# AWR2243_PMIC.net
KiCad netlist of a schematic drawn in Altium Designer
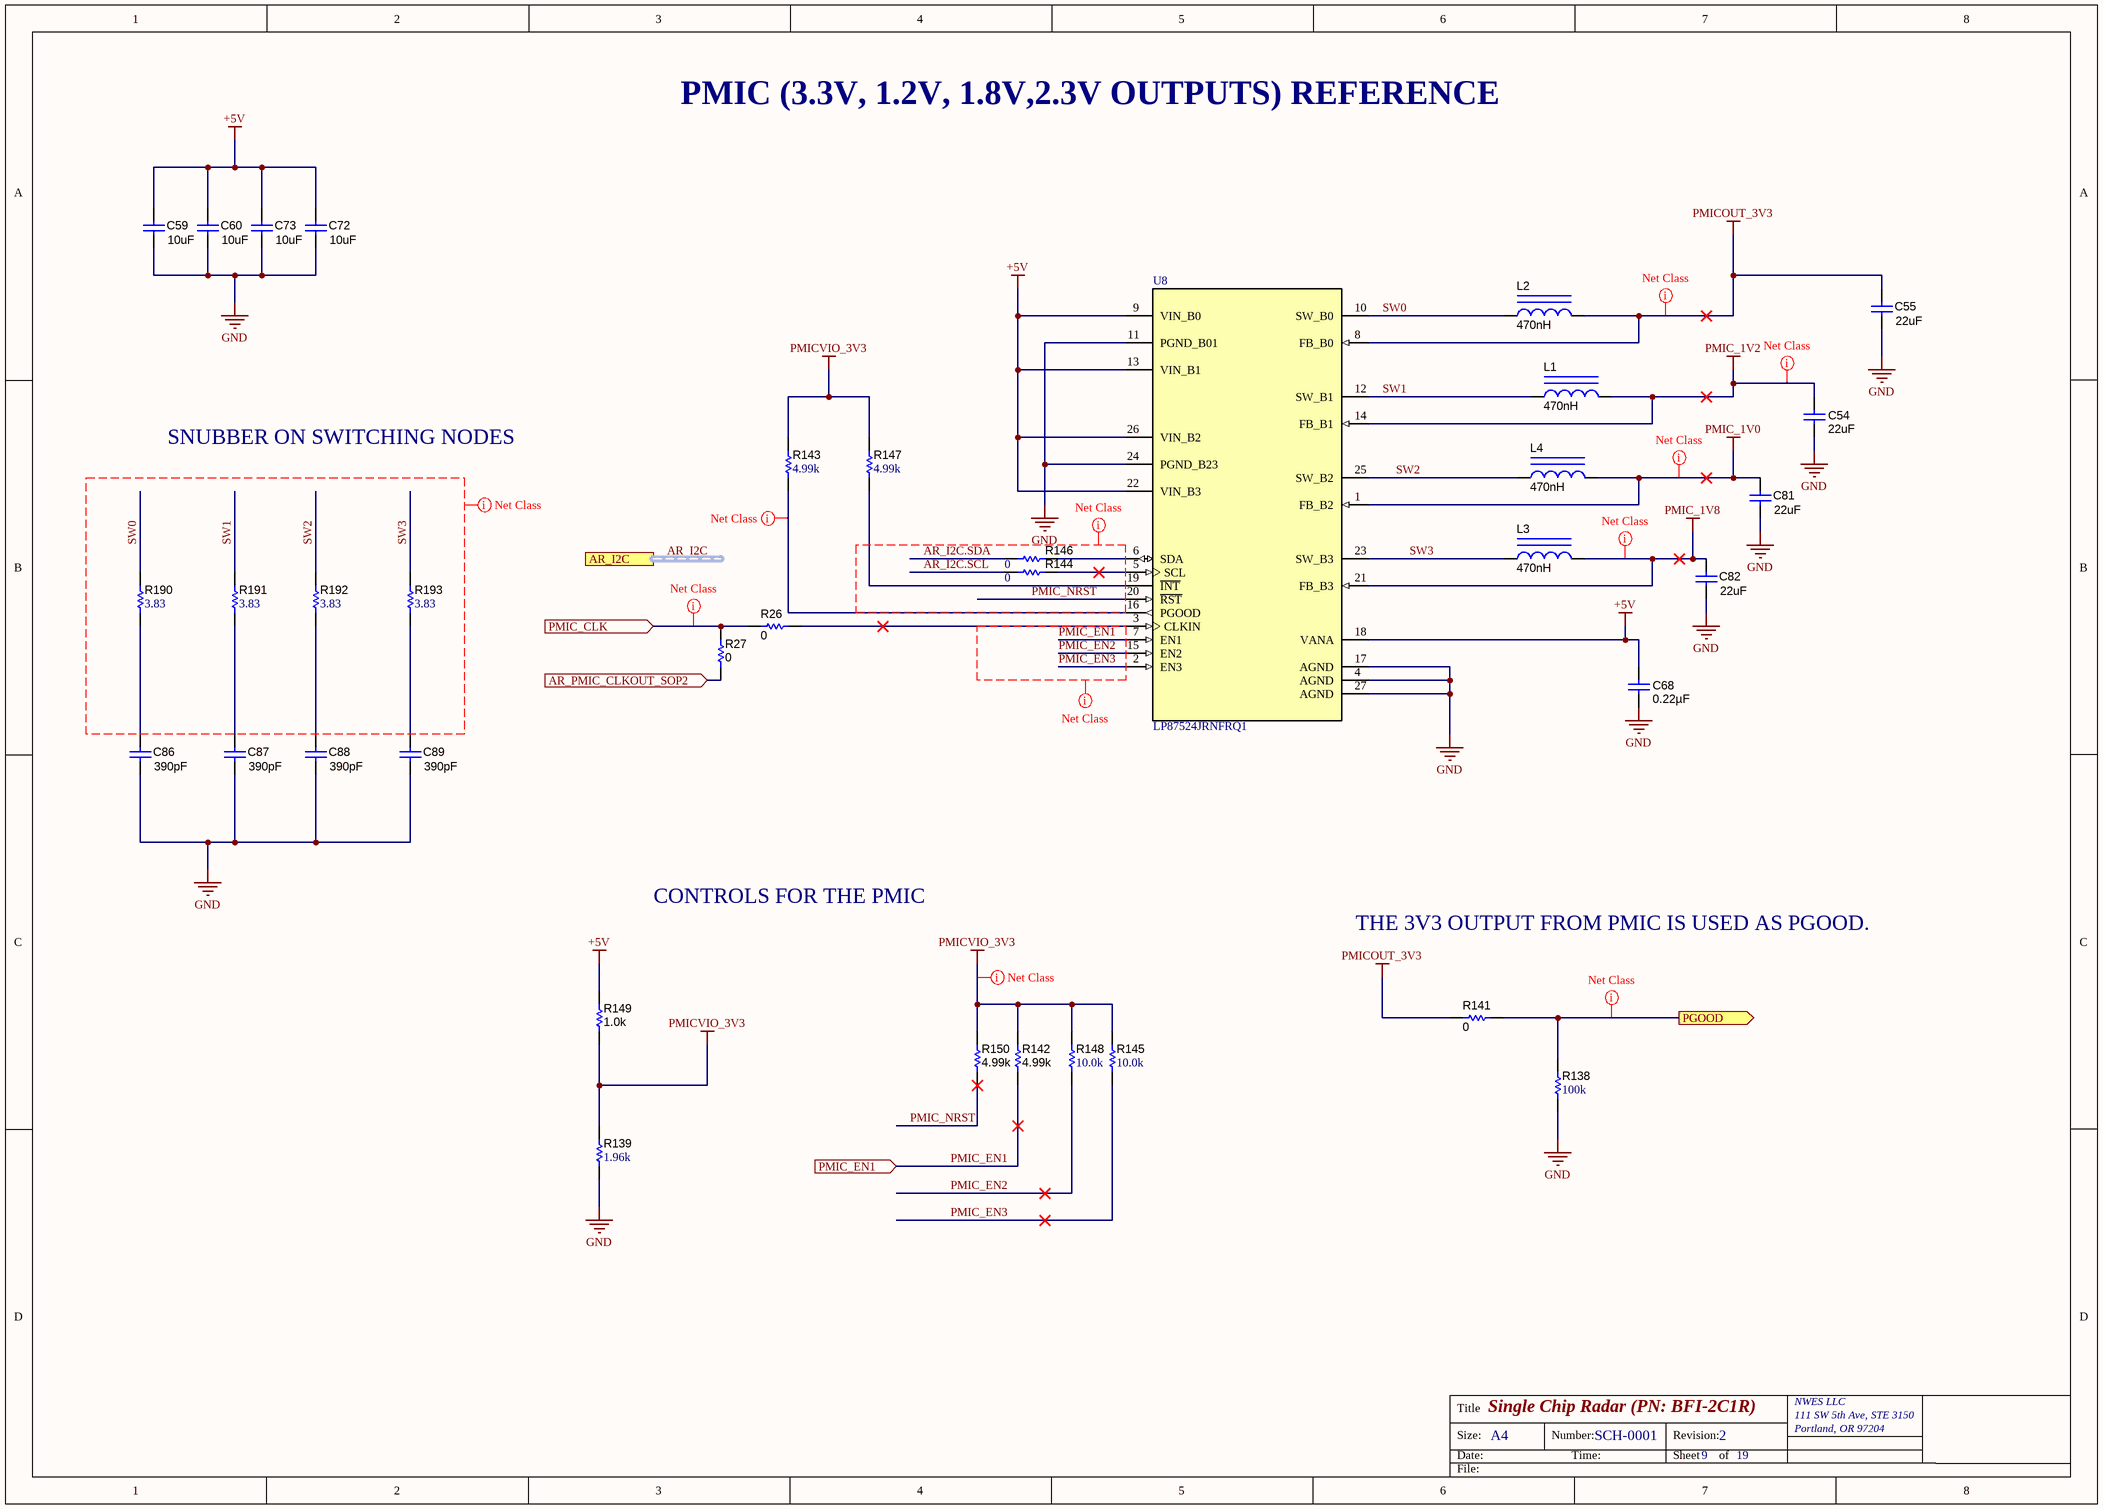
[diagram p0: AWR2243_PMIC.SchDoc]

(export (version "E")
  (design (tool "Eeschema 10.0.6"))
  (components
    (comp (ref "C54")
      (value "GCM31CR71A226KE02")
      (footprint "1206_180")
      (description "CAP, CERM, 22 uF, 10 V, +/- 10%, X7R, AEC-Q200 Grade 1, 1206")
      (fields
        (field (name "MANUFACTURER") "MuRata")
        (field (name "VALUEDISPLAYED") "22uF")
        (field (name "PUBLISHER") "Texas Instruments")
      )
      (libsource (lib "Altium Vault - TI") (part "CMP-0008811-2"))
    )
    (comp (ref "C55")
      (value "GCM31CR71A226KE02")
      (footprint "1206_180")
      (description "CAP, CERM, 22 uF, 10 V, +/- 10%, X7R, AEC-Q200 Grade 1, 1206")
      (fields
        (field (name "MANUFACTURER") "MuRata")
        (field (name "VALUEDISPLAYED") "22uF")
        (field (name "PUBLISHER") "Texas Instruments")
      )
      (libsource (lib "Altium Vault - TI") (part "Capacitor"))
    )
    (comp (ref "C59")
      (value "GCM21BR71A106KE22L")
      (footprint "0805_HV1")
      (description "CAP, CERM, 10 uF, 10 V, +/- 10%, X7R, 0805")
      (fields
        (field (name "MANUFACTURER") "MuRata")
        (field (name "VALUEDISPLAYED") "10uF")
        (field (name "PUBLISHER") "Texas Instruments")
      )
      (libsource (lib "Altium Vault - TI") (part "CMP-0008017-2"))
    )
    (comp (ref "C60")
      (value "GCM21BR71A106KE22L")
      (footprint "0805_HV1")
      (description "CAP, CERM, 10 uF, 10 V, +/- 10%, X7R, 0805")
      (fields
        (field (name "MANUFACTURER") "MuRata")
        (field (name "VALUEDISPLAYED") "10uF")
        (field (name "PUBLISHER") "Texas Instruments")
      )
      (libsource (lib "Altium Vault - TI") (part "CMP-0008017-2"))
    )
    (comp (ref "C68")
      (value "GCM155R71C224KE02D")
      (footprint "0402L")
      (description "CAP, CERM, 0.22 µF, 16 V,+/- 10%, X7R, AEC-Q200 Grade 1, 0402")
      (fields (field (name "MANUFACTURER") "MuRata") (field (name "VALUEDISPLAYED") "0.22µF"))
      (libsource (lib "Altium Vault - TI") (part "CMP-0078265-1"))
    )
    (comp (ref "C72")
      (value "GCM21BR71A106KE22L")
      (footprint "0805_HV1")
      (description "CAP, CERM, 10 uF, 10 V, +/- 10%, X7R, 0805")
      (fields
        (field (name "MANUFACTURER") "MuRata")
        (field (name "VALUEDISPLAYED") "10uF")
        (field (name "PUBLISHER") "Texas Instruments")
      )
      (libsource (lib "Altium Vault - TI") (part "CMP-0008017-2"))
    )
    (comp (ref "C73")
      (value "GCM21BR71A106KE22L")
      (footprint "0805_HV1")
      (description "CAP, CERM, 10 uF, 10 V, +/- 10%, X7R, 0805")
      (fields
        (field (name "MANUFACTURER") "MuRata")
        (field (name "VALUEDISPLAYED") "10uF")
        (field (name "PUBLISHER") "Texas Instruments")
      )
      (libsource (lib "Altium Vault - TI") (part "CMP-0008017-2"))
    )
    (comp (ref "C81")
      (value "GCM31CR71A226KE02")
      (footprint "1206_180")
      (description "CAP, CERM, 22 uF, 10 V, +/- 10%, X7R, AEC-Q200 Grade 1, 1206")
      (fields
        (field (name "MANUFACTURER") "MuRata")
        (field (name "VALUEDISPLAYED") "22uF")
        (field (name "PUBLISHER") "Texas Instruments")
      )
      (libsource (lib "Altium Vault - TI") (part "Capacitor"))
    )
    (comp (ref "C82")
      (value "GCM31CR71A226KE02")
      (footprint "1206_180")
      (description "CAP, CERM, 22 uF, 10 V, +/- 10%, X7R, AEC-Q200 Grade 1, 1206")
      (fields
        (field (name "MANUFACTURER") "MuRata")
        (field (name "VALUEDISPLAYED") "22uF")
        (field (name "PUBLISHER") "Texas Instruments")
      )
      (libsource (lib "Altium Vault - TI") (part "Capacitor"))
    )
    (comp (ref "C86")
      (value "GRM1555C1H391JA01D")
      (footprint "0402")
      (description "CAP, CERM, 390 pF, 50 V, +/- 5%, C0G/NP0, 0402")
      (fields
        (field (name "MANUFACTURER") "MuRata")
        (field (name "VALUEDISPLAYED") "390pF")
        (field (name "PUBLISHER") "Texas Instruments")
      )
      (libsource (lib "Altium Vault - TI") (part "Capacitor"))
    )
    (comp (ref "C87")
      (value "GRM1555C1H391JA01D")
      (footprint "0402")
      (description "CAP, CERM, 390 pF, 50 V, +/- 5%, C0G/NP0, 0402")
      (fields
        (field (name "MANUFACTURER") "MuRata")
        (field (name "VALUEDISPLAYED") "390pF")
        (field (name "PUBLISHER") "Texas Instruments")
      )
      (libsource (lib "Altium Vault - TI") (part "Capacitor"))
    )
    (comp (ref "C88")
      (value "GRM1555C1H391JA01D")
      (footprint "0402")
      (description "CAP, CERM, 390 pF, 50 V, +/- 5%, C0G/NP0, 0402")
      (fields
        (field (name "MANUFACTURER") "MuRata")
        (field (name "VALUEDISPLAYED") "390pF")
        (field (name "PUBLISHER") "Texas Instruments")
      )
      (libsource (lib "Altium Vault - TI") (part "Capacitor"))
    )
    (comp (ref "C89")
      (value "GRM1555C1H391JA01D")
      (footprint "0402")
      (description "CAP, CERM, 390 pF, 50 V, +/- 5%, C0G/NP0, 0402")
      (fields
        (field (name "MANUFACTURER") "MuRata")
        (field (name "VALUEDISPLAYED") "390pF")
        (field (name "PUBLISHER") "Texas Instruments")
      )
      (libsource (lib "Altium Vault - TI") (part "Capacitor"))
    )
    (comp (ref "L1")
      (value "DFE252012P-R47M=P2")
      (footprint "DFE252012P")
      (description "Inductor, Shielded, 470 nH, 4.7 A, 0.021 ohm, SMD")
      (fields
        (field (name "MANUFACTURER") "MuRata Toko")
        (field (name "VALUEDISPLAYED") "470nH")
        (field (name "PUBLISHER") "Texas Instruments")
      )
      (libsource (lib "Altium Vault - TI") (part "Inductor_Iron"))
    )
    (comp (ref "L2")
      (value "DFE252012P-R47M=P2")
      (footprint "DFE252012P")
      (description "Inductor, Shielded, 470 nH, 4.7 A, 0.021 ohm, SMD")
      (fields
        (field (name "MANUFACTURER") "MuRata Toko")
        (field (name "VALUEDISPLAYED") "470nH")
        (field (name "PUBLISHER") "Texas Instruments")
      )
      (libsource (lib "Altium Vault - TI") (part "Inductor_Iron"))
    )
    (comp (ref "L3")
      (value "DFE252012P-R47M=P2")
      (footprint "DFE252012P")
      (description "Inductor, Shielded, 470 nH, 4.7 A, 0.021 ohm, SMD")
      (fields
        (field (name "MANUFACTURER") "MuRata Toko")
        (field (name "VALUEDISPLAYED") "470nH")
        (field (name "PUBLISHER") "Texas Instruments")
      )
      (libsource (lib "Altium Vault - TI") (part "Inductor_Iron"))
    )
    (comp (ref "L4")
      (value "DFE252012P-R47M=P2")
      (footprint "DFE252012P")
      (description "Inductor, Shielded, 470 nH, 4.7 A, 0.021 ohm, SMD")
      (fields
        (field (name "MANUFACTURER") "MuRata Toko")
        (field (name "VALUEDISPLAYED") "470nH")
        (field (name "PUBLISHER") "Texas Instruments")
      )
      (libsource (lib "Altium Vault - TI") (part "Inductor_Iron"))
    )
    (comp (ref "R26")
      (value "ERJ-2GE0R00X")
      (footprint "0402")
      (description "RES, 0, 5%, 0.063 W, 0402")
      (fields
        (field (name "MANUFACTURER") "Panasonic")
        (field (name "VALUEDISPLAYED") "0")
        (field (name "PUBLISHER") "Texas Instruments")
      )
      (libsource (lib "Radar FPGA RF") (part "CMP-0026992-2"))
    )
    (comp (ref "R27")
      (value "ERJ-2GE0R00X")
      (footprint "0402")
      (description "RES, 0, 5%, 0.063 W, 0402")
      (fields
        (field (name "MANUFACTURER") "Panasonic")
        (field (name "VALUEDISPLAYED") "0")
        (field (name "PUBLISHER") "Texas Instruments")
      )
      (libsource (lib "Radar FPGA RF") (part "CMP-0026992-2"))
    )
    (comp (ref "R138")
      (value "CRCW0402100KFKED")
      (footprint "0402L")
      (description "RES, 100 k, 1%, 0.063 W, AEC-Q200 Grade 0, 0402")
      (fields (field (name "MANUFACTURER") "Vishay-Dale") (field (name "VALUEDISPLAYED") "100k"))
      (libsource (lib "Altium Vault - TI") (part "Resistor"))
    )
    (comp (ref "R139")
      (value "CRCW04021K96FKED")
      (footprint "0402L")
      (description "RES, 1.96 k, 1%, 0.063 W, AEC-Q200 Grade 0, 0402")
      (fields (field (name "MANUFACTURER") "Vishay-Dale") (field (name "VALUEDISPLAYED") "1.96k"))
      (libsource (lib "Altium Vault - TI") (part "Resistor"))
    )
    (comp (ref "R141")
      (value "ERJ-2GE0R00X")
      (footprint "0402L")
      (description "RES, 0, 5%, 0.063 W, 0402")
      (fields
        (field (name "MANUFACTURER") "Panasonic")
        (field (name "VALUEDISPLAYED") "0")
        (field (name "PUBLISHER") "Texas Instruments")
      )
      (libsource (lib "Altium Vault - TI") (part "Resistor"))
    )
    (comp (ref "R142")
      (value "ERJ-2RKF4991X")
      (footprint "0402L")
      (description "RES, 4.99 k, 1%, 0.1 W, AEC-Q200 Grade 0, 0402")
      (fields
        (field (name "MANUFACTURER") "Panasonic")
        (field (name "VALUEDISPLAYED") "4.99k")
        (field (name "PUBLISHER") "Texas Instruments")
      )
      (libsource (lib "Altium Vault - TI") (part "Resistor"))
    )
    (comp (ref "R143")
      (value "CRCW04024K99FKED")
      (footprint "0402L")
      (description "RES, 4.99 k, 1%, 0.063 W, AEC-Q200 Grade 0, 0402")
      (fields (field (name "MANUFACTURER") "Vishay-Dale") (field (name "VALUEDISPLAYED") "4.99k"))
      (libsource (lib "Altium Vault - TI") (part "Resistor"))
    )
    (comp (ref "R144")
      (value "CRCW02010000Z0ED")
      (footprint "0201_Silk")
      (description "RES, 0, 5%, 0.05 W, 0201")
      (fields (field (name "MANUFACTURER") "Vishay-Dale") (field (name "VALUEDISPLAYED") "0"))
      (libsource (lib "Altium Vault - TI") (part "Resistor"))
    )
    (comp (ref "R145")
      (value "CRCW040210K0FKED")
      (footprint "0402L")
      (description "RES, 10.0 k, 1%, 0.063 W, AEC-Q200 Grade 0, 0402")
      (fields (field (name "MANUFACTURER") "Vishay-Dale") (field (name "VALUEDISPLAYED") "10.0k"))
      (libsource (lib "Altium Vault - TI") (part "CMP-0025958-3"))
    )
    (comp (ref "R146")
      (value "CRCW02010000Z0ED")
      (footprint "0201_Silk")
      (description "RES, 0, 5%, 0.05 W, 0201")
      (fields (field (name "MANUFACTURER") "Vishay-Dale") (field (name "VALUEDISPLAYED") "0"))
      (libsource (lib "Altium Vault - TI") (part "Resistor"))
    )
    (comp (ref "R147")
      (value "CRCW04024K99FKED")
      (footprint "0402L")
      (description "RES, 4.99 k, 1%, 0.063 W, AEC-Q200 Grade 0, 0402")
      (fields (field (name "MANUFACTURER") "Vishay-Dale") (field (name "VALUEDISPLAYED") "4.99k"))
      (libsource (lib "Altium Vault - TI") (part "Resistor"))
    )
    (comp (ref "R148")
      (value "CRCW040210K0FKED")
      (footprint "0402L")
      (description "RES, 10.0 k, 1%, 0.063 W, AEC-Q200 Grade 0, 0402")
      (fields (field (name "MANUFACTURER") "Vishay-Dale") (field (name "VALUEDISPLAYED") "10.0k"))
      (libsource (lib "Altium Vault - TI") (part "Resistor"))
    )
    (comp (ref "R149")
      (value "ERJ-2GEJ102X")
      (footprint "0402L")
      (description "RES, 1.0 k, 5%, 0.1 W, AEC-Q200 Grade 0, 0402")
      (fields (field (name "MANUFACTURER") "Panasonic") (field (name "VALUEDISPLAYED") "1.0k"))
      (libsource (lib "Altium Vault - TI") (part "Resistor"))
    )
    (comp (ref "R150")
      (value "ERJ-2RKF4991X")
      (footprint "0402L")
      (description "RES, 4.99 k, 1%, 0.1 W, AEC-Q200 Grade 0, 0402")
      (fields
        (field (name "MANUFACTURER") "Panasonic")
        (field (name "VALUEDISPLAYED") "4.99k")
        (field (name "PUBLISHER") "Texas Instruments")
      )
      (libsource (lib "Altium Vault - TI") (part "Resistor"))
    )
    (comp (ref "R190")
      (value "CRCW04023R83FKED")
      (footprint "0402L")
      (description "RES, 3.83, 1%, 0.063 W, AEC-Q200 Grade 0, 0402")
      (fields (field (name "MANUFACTURER") "Vishay-Dale") (field (name "VALUEDISPLAYED") "3.83"))
      (libsource (lib "Altium Vault - TI") (part "Resistor"))
    )
    (comp (ref "R191")
      (value "CRCW04023R83FKED")
      (footprint "0402L")
      (description "RES, 3.83, 1%, 0.063 W, AEC-Q200 Grade 0, 0402")
      (fields (field (name "MANUFACTURER") "Vishay-Dale") (field (name "VALUEDISPLAYED") "3.83"))
      (libsource (lib "Altium Vault - TI") (part "Resistor"))
    )
    (comp (ref "R192")
      (value "CRCW04023R83FKED")
      (footprint "0402L")
      (description "RES, 3.83, 1%, 0.063 W, AEC-Q200 Grade 0, 0402")
      (fields (field (name "MANUFACTURER") "Vishay-Dale") (field (name "VALUEDISPLAYED") "3.83"))
      (libsource (lib "Altium Vault - TI") (part "Resistor"))
    )
    (comp (ref "R193")
      (value "CRCW04023R83FKED")
      (footprint "0402L")
      (description "RES, 3.83, 1%, 0.063 W, AEC-Q200 Grade 0, 0402")
      (fields (field (name "MANUFACTURER") "Vishay-Dale") (field (name "VALUEDISPLAYED") "3.83"))
      (libsource (lib "Altium Vault - TI") (part "Resistor"))
    )
    (comp (ref "U8")
      (value "LP87524JRNFRQ1")
      (footprint "RNF0026C")
      (description "4-A + 2.5-A + Two 1.5-A Buck Converters With Integrated Switches, RNF0026C (VQFN-HR-26)")
      (fields
        (field (name "ALTERNATE PARTNUMBER") "LP87524JRNFTQ1")
        (field (name "MANUFACTURER") "Texas Instruments")
        (field (name "PARTNUMBER") "LP87524JRNFRQ1")
      )
      (libsource (lib "Altium Vault - TI") (part "CMP-0079120-1"))
    )
  )
  (nets
    (net (code "2") (name "+5V") (class "Default")
      (node (ref "C59") (pin "2") (pinfunction "2_2") (pintype "passive"))
      (node (ref "C60") (pin "2") (pinfunction "2_2") (pintype "passive"))
      (node (ref "C68") (pin "2") (pinfunction "2_2") (pintype "passive"))
      (node (ref "C72") (pin "2") (pinfunction "2_2") (pintype "passive"))
      (node (ref "C73") (pin "2") (pinfunction "2_2") (pintype "passive"))
      (node (ref "R149") (pin "2") (pinfunction "2_2") (pintype "passive"))
      (node (ref "U8") (pin "13") (pinfunction "VIN_B1_13") (pintype "power_in"))
      (node (ref "U8") (pin "18") (pinfunction "VANA_18") (pintype "power_in"))
      (node (ref "U8") (pin "22") (pinfunction "VIN_B3_22") (pintype "power_in"))
      (node (ref "U8") (pin "26") (pinfunction "VIN_B2_26") (pintype "power_in"))
      (node (ref "U8") (pin "9") (pinfunction "VIN_B0_9") (pintype "power_in"))
    )
    (net (code "3") (name "/AR_I2C.SCL") (class "Default")
      (node (ref "R144") (pin "1") (pinfunction "1_1") (pintype "passive"))
    )
    (net (code "4") (name "/AR_I2C.SDA") (class "Default")
      (node (ref "R146") (pin "2") (pinfunction "2_2") (pintype "passive"))
    )
    (net (code "5") (name "/AR_PMIC_CLKOUT_SOP2") (class "Default")
      (node (ref "R27") (pin "2") (pinfunction "2_2") (pintype "passive"))
    )
    (net (code "6") (name "/PGOOD") (class "Default")
      (node (ref "R138") (pin "2") (pinfunction "2_2") (pintype "passive"))
      (node (ref "R141") (pin "2") (pinfunction "2_2") (pintype "passive"))
    )
    (net (code "7") (name "/PMIC_CLK") (class "Default")
      (node (ref "R26") (pin "1") (pinfunction "1_1") (pintype "passive"))
      (node (ref "R27") (pin "1") (pinfunction "1_1") (pintype "passive"))
    )
    (net (code "8") (name "/PMIC_EN1") (class "Default")
      (node (ref "R142") (pin "1") (pinfunction "1_1") (pintype "passive"))
      (node (ref "U8") (pin "7") (pinfunction "EN1_7") (pintype "input"))
    )
    (net (code "9") (name "/PMIC_EN2") (class "Default")
      (node (ref "R148") (pin "1") (pinfunction "1_1") (pintype "passive"))
      (node (ref "U8") (pin "15") (pinfunction "EN2_15") (pintype "input"))
    )
    (net (code "10") (name "/PMIC_EN3") (class "Default")
      (node (ref "R145") (pin "1") (pinfunction "1_1") (pintype "passive"))
      (node (ref "U8") (pin "2") (pinfunction "EN3_2") (pintype "input"))
    )
    (net (code "11") (name "/PMIC_NRST") (class "Default")
      (node (ref "R150") (pin "2") (pinfunction "2_2") (pintype "passive"))
      (node (ref "U8") (pin "20") (pinfunction "RST_20") (pintype "input"))
    )
    (net (code "12") (name "/SW0") (class "Default")
      (node (ref "L2") (pin "1") (pinfunction "1_1") (pintype "passive"))
      (node (ref "R190") (pin "2") (pinfunction "2_2") (pintype "passive"))
      (node (ref "U8") (pin "10") (pinfunction "SW_B0_10") (pintype "power_in"))
    )
    (net (code "13") (name "/SW1") (class "Default")
      (node (ref "L1") (pin "1") (pinfunction "1_1") (pintype "passive"))
      (node (ref "R191") (pin "2") (pinfunction "2_2") (pintype "passive"))
      (node (ref "U8") (pin "12") (pinfunction "SW_B1_12") (pintype "power_in"))
    )
    (net (code "14") (name "/SW2") (class "Default")
      (node (ref "L4") (pin "1") (pinfunction "1_1") (pintype "passive"))
      (node (ref "R192") (pin "2") (pinfunction "2_2") (pintype "passive"))
      (node (ref "U8") (pin "25") (pinfunction "SW_B2_25") (pintype "power_in"))
    )
    (net (code "15") (name "/SW3") (class "Default")
      (node (ref "L3") (pin "1") (pinfunction "1_1") (pintype "passive"))
      (node (ref "R193") (pin "2") (pinfunction "2_2") (pintype "passive"))
      (node (ref "U8") (pin "23") (pinfunction "SW_B3_23") (pintype "power_in"))
    )
    (net (code "17") (name "GND") (class "Default")
      (node (ref "C54") (pin "1") (pinfunction "1_1") (pintype "passive"))
      (node (ref "C55") (pin "1") (pinfunction "1_1") (pintype "passive"))
      (node (ref "C59") (pin "1") (pinfunction "1_1") (pintype "passive"))
      (node (ref "C60") (pin "1") (pinfunction "1_1") (pintype "passive"))
      (node (ref "C68") (pin "1") (pinfunction "1_1") (pintype "passive"))
      (node (ref "C72") (pin "1") (pinfunction "1_1") (pintype "passive"))
      (node (ref "C73") (pin "1") (pinfunction "1_1") (pintype "passive"))
      (node (ref "C81") (pin "1") (pinfunction "1_1") (pintype "passive"))
      (node (ref "C82") (pin "1") (pinfunction "1_1") (pintype "passive"))
      (node (ref "C86") (pin "2") (pinfunction "2_2") (pintype "passive"))
      (node (ref "C87") (pin "2") (pinfunction "2_2") (pintype "passive"))
      (node (ref "C88") (pin "2") (pinfunction "2_2") (pintype "passive"))
      (node (ref "C89") (pin "2") (pinfunction "2_2") (pintype "passive"))
      (node (ref "R138") (pin "1") (pinfunction "1_1") (pintype "passive"))
      (node (ref "R139") (pin "1") (pinfunction "1_1") (pintype "passive"))
      (node (ref "U8") (pin "11") (pinfunction "PGND_B01_11") (pintype "power_in"))
      (node (ref "U8") (pin "17") (pinfunction "AGND_17") (pintype "power_in"))
      (node (ref "U8") (pin "24") (pinfunction "PGND_B23_24") (pintype "power_in"))
      (node (ref "U8") (pin "27") (pinfunction "AGND_27") (pintype "power_in"))
      (node (ref "U8") (pin "4") (pinfunction "AGND_4") (pintype "power_in"))
    )
    (net (code "18") (name "Net-(C86-Pad1)") (class "Default")
      (node (ref "C86") (pin "1") (pinfunction "1_1") (pintype "passive"))
      (node (ref "R190") (pin "1") (pinfunction "1_1") (pintype "passive"))
    )
    (net (code "19") (name "Net-(C87-Pad1)") (class "Default")
      (node (ref "C87") (pin "1") (pinfunction "1_1") (pintype "passive"))
      (node (ref "R191") (pin "1") (pinfunction "1_1") (pintype "passive"))
    )
    (net (code "20") (name "Net-(C88-Pad1)") (class "Default")
      (node (ref "C88") (pin "1") (pinfunction "1_1") (pintype "passive"))
      (node (ref "R192") (pin "1") (pinfunction "1_1") (pintype "passive"))
    )
    (net (code "21") (name "Net-(C89-Pad1)") (class "Default")
      (node (ref "C89") (pin "1") (pinfunction "1_1") (pintype "passive"))
      (node (ref "R193") (pin "1") (pinfunction "1_1") (pintype "passive"))
    )
    (net (code "22") (name "Net-(U8-CLKIN)") (class "Default")
      (node (ref "R26") (pin "2") (pinfunction "2_2") (pintype "passive"))
      (node (ref "U8") (pin "3") (pinfunction "CLKIN_3") (pintype "input"))
    )
    (net (code "23") (name "Net-(U8-INT)") (class "Default")
      (node (ref "R147") (pin "1") (pinfunction "1_1") (pintype "passive"))
      (node (ref "U8") (pin "19") (pinfunction "INT_19") (pintype "open_collector"))
    )
    (net (code "24") (name "Net-(U8-PGOOD)") (class "Default")
      (node (ref "R143") (pin "1") (pinfunction "1_1") (pintype "passive"))
      (node (ref "U8") (pin "16") (pinfunction "PGOOD_16") (pintype "output"))
    )
    (net (code "25") (name "Net-(U8-SCL)") (class "Default")
      (node (ref "R144") (pin "2") (pinfunction "2_2") (pintype "passive"))
      (node (ref "U8") (pin "5") (pinfunction "SCL_5") (pintype "input"))
    )
    (net (code "26") (name "Net-(U8-SDA)") (class "Default")
      (node (ref "R146") (pin "1") (pinfunction "1_1") (pintype "passive"))
      (node (ref "U8") (pin "6") (pinfunction "SDA_6") (pintype "bidirectional"))
    )
    (net (code "27") (name "PMICOUT_3V3") (class "Default")
      (node (ref "C55") (pin "2") (pinfunction "2_2") (pintype "passive"))
      (node (ref "L2") (pin "2") (pinfunction "2_2") (pintype "passive"))
      (node (ref "R141") (pin "1") (pinfunction "1_1") (pintype "passive"))
      (node (ref "U8") (pin "8") (pinfunction "FB_B0_8") (pintype "input"))
    )
    (net (code "28") (name "PMICVIO_3V3") (class "Default")
      (node (ref "R139") (pin "2") (pinfunction "2_2") (pintype "passive"))
      (node (ref "R142") (pin "2") (pinfunction "2_2") (pintype "passive"))
      (node (ref "R143") (pin "2") (pinfunction "2_2") (pintype "passive"))
      (node (ref "R145") (pin "2") (pinfunction "2_2") (pintype "passive"))
      (node (ref "R147") (pin "2") (pinfunction "2_2") (pintype "passive"))
      (node (ref "R148") (pin "2") (pinfunction "2_2") (pintype "passive"))
      (node (ref "R149") (pin "1") (pinfunction "1_1") (pintype "passive"))
      (node (ref "R150") (pin "1") (pinfunction "1_1") (pintype "passive"))
    )
    (net (code "29") (name "PMIC_1V0") (class "Default")
      (node (ref "C81") (pin "2") (pinfunction "2_2") (pintype "passive"))
      (node (ref "L4") (pin "2") (pinfunction "2_2") (pintype "passive"))
      (node (ref "U8") (pin "1") (pinfunction "FB_B2_1") (pintype "input"))
    )
    (net (code "30") (name "PMIC_1V2") (class "Default")
      (node (ref "C54") (pin "2") (pinfunction "2_2") (pintype "passive"))
      (node (ref "L1") (pin "2") (pinfunction "2_2") (pintype "passive"))
      (node (ref "U8") (pin "14") (pinfunction "FB_B1_14") (pintype "input"))
    )
    (net (code "31") (name "PMIC_1V8") (class "Default")
      (node (ref "C82") (pin "2") (pinfunction "2_2") (pintype "passive"))
      (node (ref "L3") (pin "2") (pinfunction "2_2") (pintype "passive"))
      (node (ref "U8") (pin "21") (pinfunction "FB_B3_21") (pintype "input"))
    )
  )
)
